# schematic_easyeda.net
KiCad netlist of a schematic drawn in EasyEDA
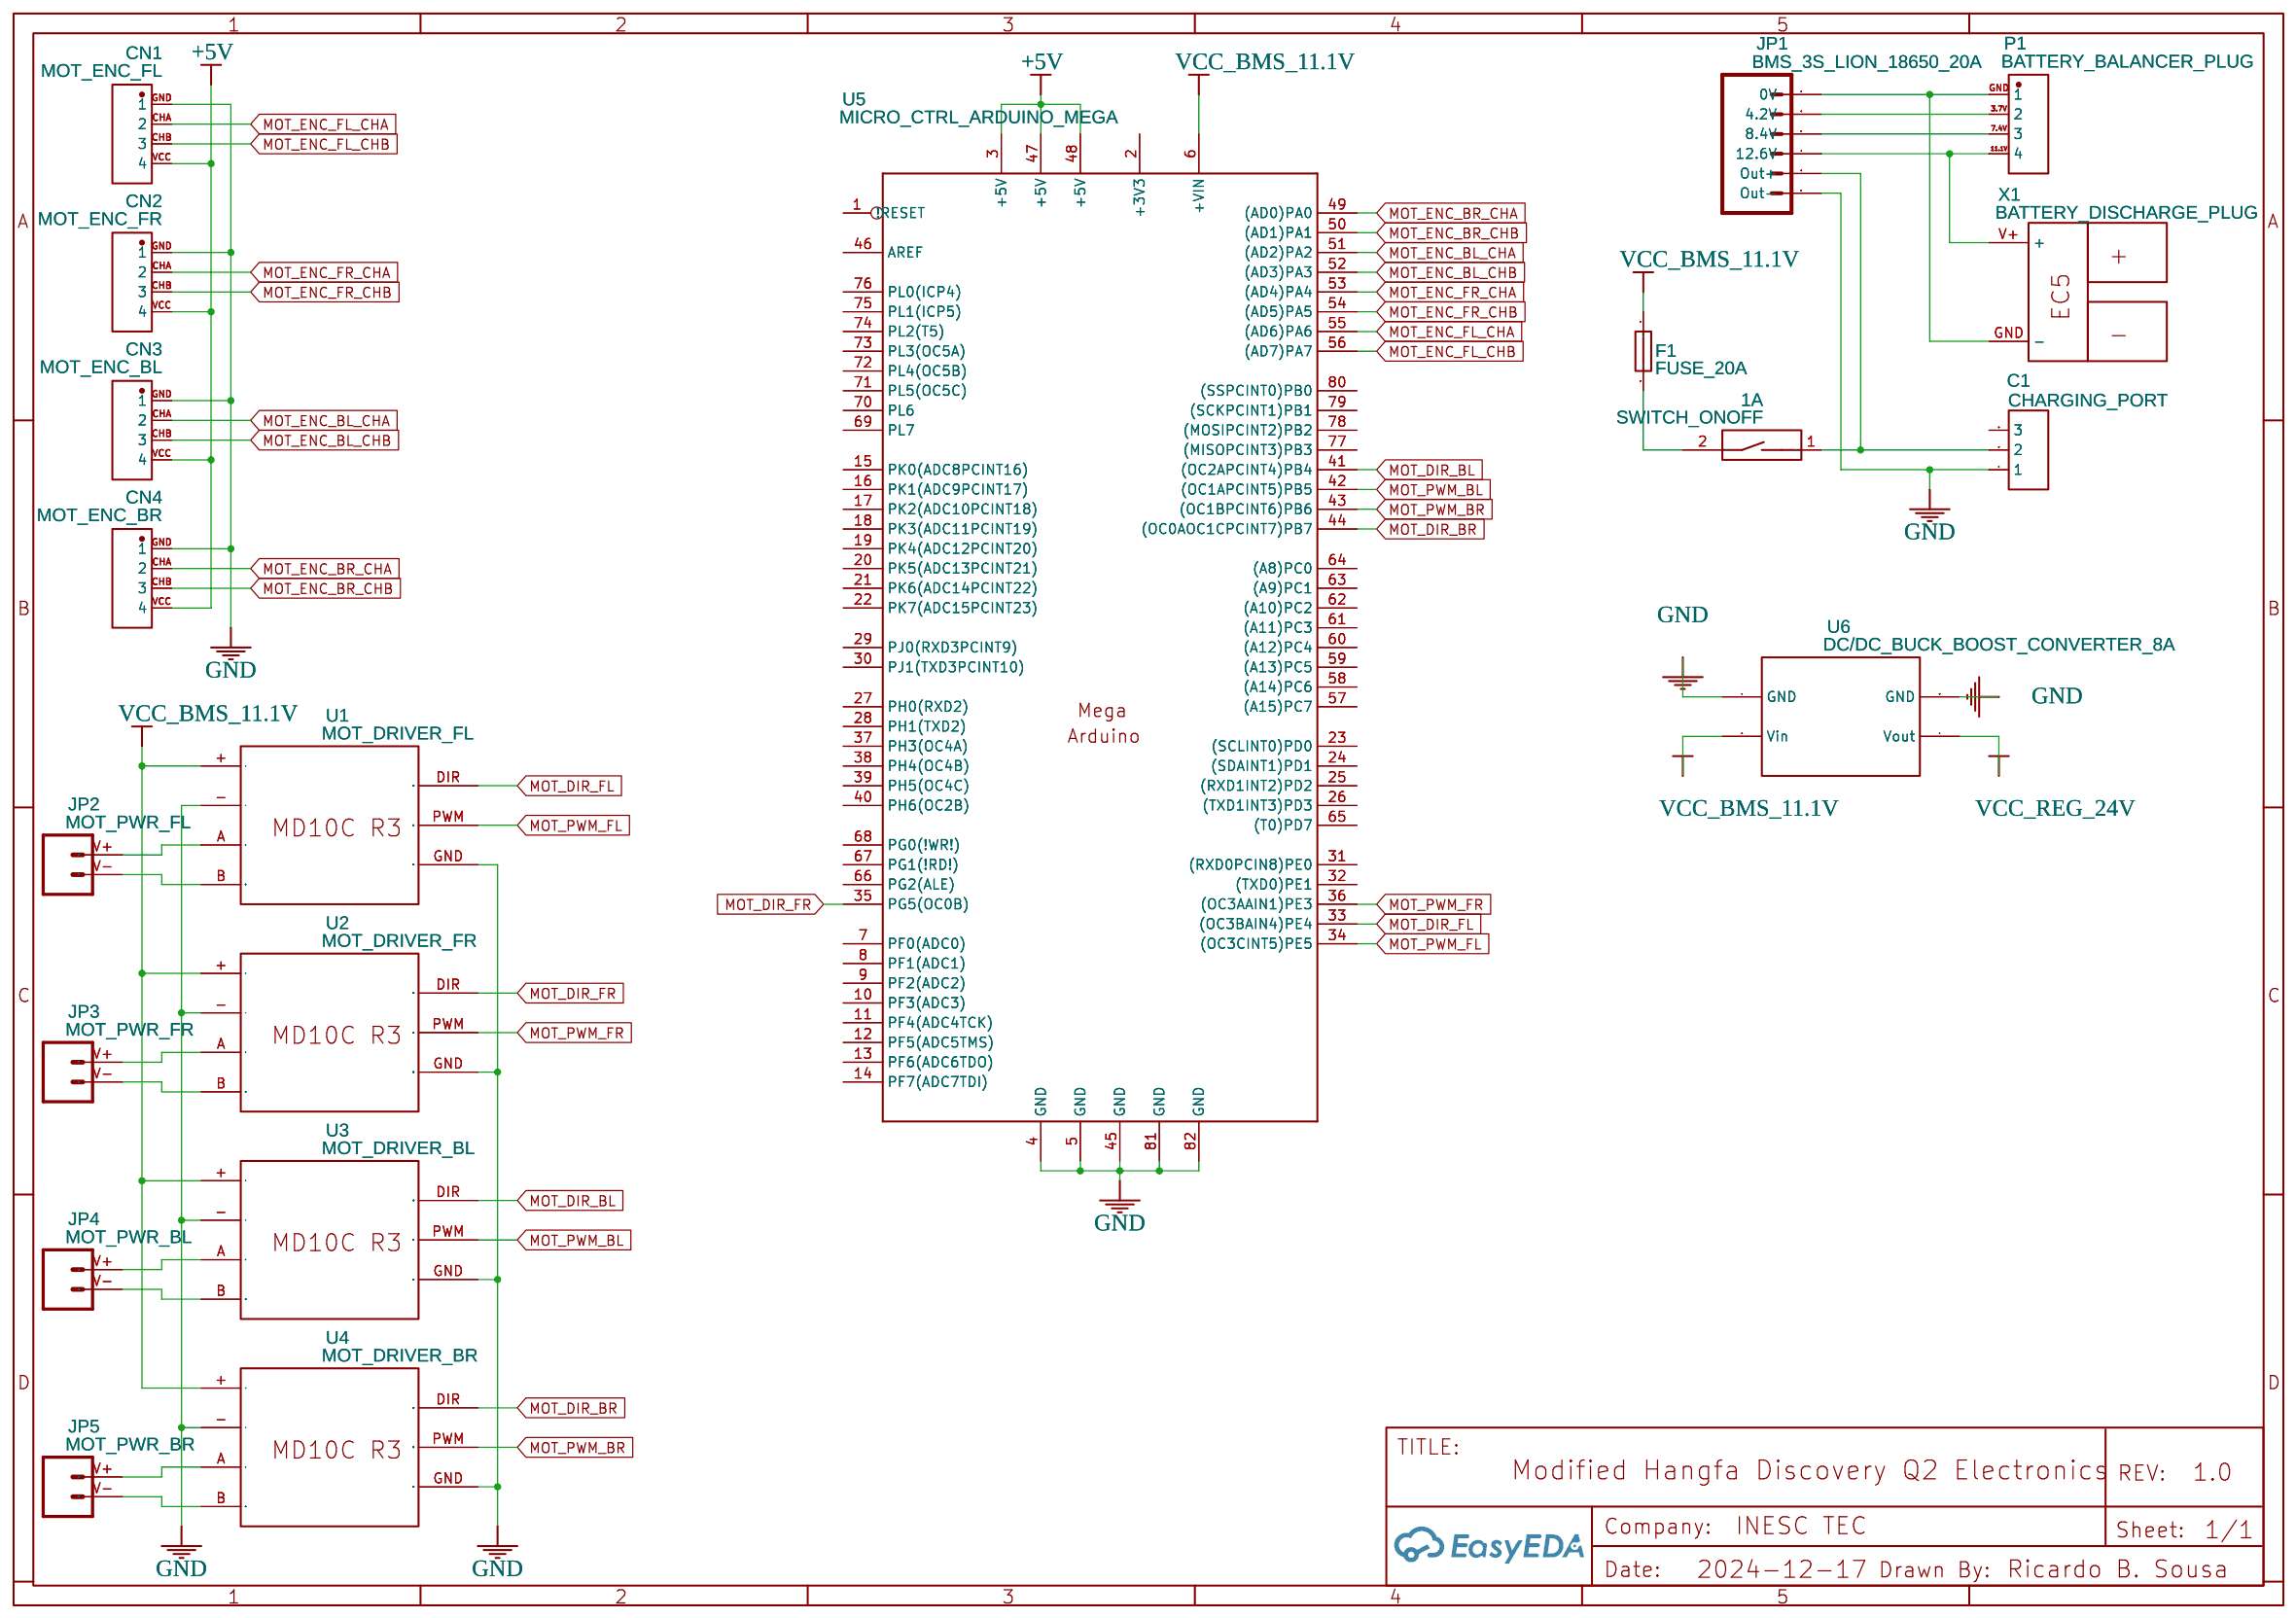
[diagram p0: schematic sheet]

(export (version "E")
  (design (tool "Eeschema 10.0.6"))
  (components
    (comp (ref "1A")
      (value "SWITCH_ONOFF")
      (fields (field (name "Manufacturer Part") "DIP switchEI-08") (field (name "Manufacturer") "DIP"))
      (libsource (lib "") (part "Switch"))
    )
    (comp (ref "C1") (value "CHARGING_PORT") (libsource (lib "") (part "HDR-F-2.54_1x3")))
    (comp (ref "CN1") (value "MOT_ENC_FL") (libsource (lib "") (part "JST-XH2.54 4P")))
    (comp (ref "CN2") (value "MOT_ENC_FR") (libsource (lib "") (part "JST-XH2.54 4P")))
    (comp (ref "CN3") (value "MOT_ENC_BL") (libsource (lib "") (part "JST-XH2.54 4P")))
    (comp (ref "CN4") (value "MOT_ENC_BR") (libsource (lib "") (part "JST-XH2.54 4P")))
    (comp (ref "F1")
      (value "FUSE_20A")
      (fields
        (field (name "Manufacturer Part") "0326025.MXP")
        (field (name "Manufacturer") "Littelfuse(美国力特)")
      )
      (libsource (lib "") (part "Fuse"))
    )
    (comp (ref "JP1") (value "BMS_3S_LION_18650_20A") (libsource (lib "") (part "MY BMS-3S-20A")))
    (comp (ref "JP2") (value "MOT_PWR_FL") (libsource (lib "") (part "M02POLAR")))
    (comp (ref "JP3") (value "MOT_PWR_FR") (libsource (lib "") (part "M02POLAR")))
    (comp (ref "JP4") (value "MOT_PWR_BL") (libsource (lib "") (part "M02POLAR")))
    (comp (ref "JP5") (value "MOT_PWR_BR") (libsource (lib "") (part "M02POLAR")))
    (comp (ref "P1")
      (value "BATTERY_BALANCER_PLUG")
      (fields (field (name "Manufacturer Part") "XH-2.54-4P"))
      (libsource (lib "") (part "XH-2.54-4P"))
    )
    (comp (ref "U1")
      (value "MOT_DRIVER_FL")
      (fields (field (name "Manufacturer") "Cytron"))
      (libsource (lib "") (part "MD10C-R3"))
    )
    (comp (ref "U2")
      (value "MOT_DRIVER_FR")
      (fields (field (name "Manufacturer") "Cytron"))
      (libsource (lib "") (part "MD10C-R3"))
    )
    (comp (ref "U3")
      (value "MOT_DRIVER_BL")
      (fields (field (name "Manufacturer") "Cytron"))
      (libsource (lib "") (part "MD10C-R3"))
    )
    (comp (ref "U4")
      (value "MOT_DRIVER_BR")
      (fields (field (name "Manufacturer") "Cytron"))
      (libsource (lib "") (part "MD10C-R3"))
    )
    (comp (ref "U5") (value "MICRO_CTRL_ARDUINO_MEGA") (libsource (lib "") (part "MEGAARDUINO_1")))
    (comp (ref "U6")
      (value "DC/DC_BUCK_BOOST_CONVERTER_8A")
      (fields (field (name "Manufacturer Part") "DC-DC Converter"))
      (libsource (lib "") (part "DC-DC Converter"))
    )
    (comp (ref "X1") (value "BATTERY_DISCHARGE_PLUG") (libsource (lib "") (part "EC5")))
  )
  (nets
    (net (code "1") (name "+5V") (class "Default")
      (node (ref "CN1") (pin "VCC") (pinfunction "4_VCC") (pintype "unspecified"))
      (node (ref "CN2") (pin "VCC") (pinfunction "4_VCC") (pintype "unspecified"))
      (node (ref "CN3") (pin "VCC") (pinfunction "4_VCC") (pintype "unspecified"))
      (node (ref "CN4") (pin "VCC") (pinfunction "4_VCC") (pintype "unspecified"))
      (node (ref "U5") (pin "3") (pinfunction "+5V_3") (pintype "passive"))
      (node (ref "U5") (pin "47") (pinfunction "+5V_47") (pintype "passive"))
      (node (ref "U5") (pin "48") (pinfunction "+5V_48") (pintype "passive"))
    )
    (net (code "2") (name "GND") (class "Default")
      (node (ref "C1") (pin "1") (pinfunction "1_1") (pintype "unspecified"))
      (node (ref "CN1") (pin "GND") (pinfunction "1_GND") (pintype "unspecified"))
      (node (ref "CN2") (pin "GND") (pinfunction "1_GND") (pintype "unspecified"))
      (node (ref "CN3") (pin "GND") (pinfunction "1_GND") (pintype "unspecified"))
      (node (ref "CN4") (pin "GND") (pinfunction "1_GND") (pintype "unspecified"))
      (node (ref "JP1") (pin "6") (pinfunction "Out-_6") (pintype "unspecified"))
      (node (ref "U1") (pin "-") (pinfunction "-_-") (pintype "unspecified"))
      (node (ref "U1") (pin "GND") (pinfunction "GND_GND") (pintype "unspecified"))
      (node (ref "U2") (pin "-") (pinfunction "-_-") (pintype "unspecified"))
      (node (ref "U2") (pin "GND") (pinfunction "GND_GND") (pintype "unspecified"))
      (node (ref "U3") (pin "-") (pinfunction "-_-") (pintype "unspecified"))
      (node (ref "U3") (pin "GND") (pinfunction "GND_GND") (pintype "unspecified"))
      (node (ref "U4") (pin "-") (pinfunction "-_-") (pintype "unspecified"))
      (node (ref "U4") (pin "GND") (pinfunction "GND_GND") (pintype "unspecified"))
      (node (ref "U5") (pin "4") (pinfunction "GND_4") (pintype "passive"))
      (node (ref "U5") (pin "45") (pinfunction "GND_45") (pintype "passive"))
      (node (ref "U5") (pin "5") (pinfunction "GND_5") (pintype "passive"))
      (node (ref "U5") (pin "81") (pinfunction "GND_81") (pintype "passive"))
      (node (ref "U5") (pin "82") (pinfunction "GND_82") (pintype "passive"))
      (node (ref "U6") (pin "1") (pinfunction "GND_1") (pintype "unspecified"))
      (node (ref "U6") (pin "3") (pinfunction "GND_3") (pintype "unspecified"))
    )
    (net (code "3") (name "MOT_DIR_BL") (class "Default")
      (node (ref "U3") (pin "DIR") (pinfunction "DIR_DIR") (pintype "unspecified"))
      (node (ref "U5") (pin "41") (pinfunction "(OC2APCINT4)PB4_41") (pintype "unspecified"))
    )
    (net (code "4") (name "MOT_DIR_BR") (class "Default")
      (node (ref "U4") (pin "DIR") (pinfunction "DIR_DIR") (pintype "unspecified"))
      (node (ref "U5") (pin "44") (pinfunction "(OC0AOC1CPCINT7)PB7_44") (pintype "unspecified"))
    )
    (net (code "5") (name "MOT_DIR_FL") (class "Default")
      (node (ref "U1") (pin "DIR") (pinfunction "DIR_DIR") (pintype "unspecified"))
      (node (ref "U5") (pin "33") (pinfunction "(OC3BAIN4)PE4_33") (pintype "unspecified"))
    )
    (net (code "6") (name "MOT_DIR_FR") (class "Default")
      (node (ref "U2") (pin "DIR") (pinfunction "DIR_DIR") (pintype "unspecified"))
      (node (ref "U5") (pin "35") (pinfunction "PG5(OC0B)_35") (pintype "unspecified"))
    )
    (net (code "7") (name "MOT_ENC_BL_CHA") (class "Default")
      (node (ref "CN3") (pin "CHA") (pinfunction "2_CHA") (pintype "unspecified"))
      (node (ref "U5") (pin "51") (pinfunction "(AD2)PA2_51") (pintype "unspecified"))
    )
    (net (code "8") (name "MOT_ENC_BL_CHB") (class "Default")
      (node (ref "CN3") (pin "CHB") (pinfunction "3_CHB") (pintype "unspecified"))
      (node (ref "U5") (pin "52") (pinfunction "(AD3)PA3_52") (pintype "unspecified"))
    )
    (net (code "9") (name "MOT_ENC_BR_CHA") (class "Default")
      (node (ref "CN4") (pin "CHA") (pinfunction "2_CHA") (pintype "unspecified"))
      (node (ref "U5") (pin "49") (pinfunction "(AD0)PA0_49") (pintype "unspecified"))
    )
    (net (code "10") (name "MOT_ENC_BR_CHB") (class "Default")
      (node (ref "CN4") (pin "CHB") (pinfunction "3_CHB") (pintype "unspecified"))
      (node (ref "U5") (pin "50") (pinfunction "(AD1)PA1_50") (pintype "unspecified"))
    )
    (net (code "11") (name "MOT_ENC_FL_CHA") (class "Default")
      (node (ref "CN1") (pin "CHA") (pinfunction "2_CHA") (pintype "unspecified"))
      (node (ref "U5") (pin "55") (pinfunction "(AD6)PA6_55") (pintype "unspecified"))
    )
    (net (code "12") (name "MOT_ENC_FL_CHB") (class "Default")
      (node (ref "CN1") (pin "CHB") (pinfunction "3_CHB") (pintype "unspecified"))
      (node (ref "U5") (pin "56") (pinfunction "(AD7)PA7_56") (pintype "unspecified"))
    )
    (net (code "13") (name "MOT_ENC_FR_CHA") (class "Default")
      (node (ref "CN2") (pin "CHA") (pinfunction "2_CHA") (pintype "unspecified"))
      (node (ref "U5") (pin "53") (pinfunction "(AD4)PA4_53") (pintype "unspecified"))
    )
    (net (code "14") (name "MOT_ENC_FR_CHB") (class "Default")
      (node (ref "CN2") (pin "CHB") (pinfunction "3_CHB") (pintype "unspecified"))
      (node (ref "U5") (pin "54") (pinfunction "(AD5)PA5_54") (pintype "unspecified"))
    )
    (net (code "15") (name "MOT_PWM_BL") (class "Default")
      (node (ref "U3") (pin "PWM") (pinfunction "PWM_PWM") (pintype "unspecified"))
      (node (ref "U5") (pin "42") (pinfunction "(OC1APCINT5)PB5_42") (pintype "unspecified"))
    )
    (net (code "16") (name "MOT_PWM_BR") (class "Default")
      (node (ref "U4") (pin "PWM") (pinfunction "PWM_PWM") (pintype "unspecified"))
      (node (ref "U5") (pin "43") (pinfunction "(OC1BPCINT6)PB6_43") (pintype "unspecified"))
    )
    (net (code "17") (name "MOT_PWM_FL") (class "Default")
      (node (ref "U1") (pin "PWM") (pinfunction "PWM_PWM") (pintype "unspecified"))
      (node (ref "U5") (pin "34") (pinfunction "(OC3CINT5)PE5_34") (pintype "unspecified"))
    )
    (net (code "18") (name "MOT_PWM_FR") (class "Default")
      (node (ref "U2") (pin "PWM") (pinfunction "PWM_PWM") (pintype "unspecified"))
      (node (ref "U5") (pin "36") (pinfunction "(OC3AAIN1)PE3_36") (pintype "unspecified"))
    )
    (net (code "19") (name "Net-(1A-Pad2)") (class "Default")
      (node (ref "1A") (pin "2") (pinfunction "2_2") (pintype "unspecified"))
      (node (ref "F1") (pin "2") (pinfunction "2_2") (pintype "unspecified"))
    )
    (net (code "20") (name "Net-(JP1-0V)") (class "Default")
      (node (ref "JP1") (pin "1") (pinfunction "0V_1") (pintype "unspecified"))
      (node (ref "P1") (pin "GND") (pinfunction "1_GND") (pintype "unspecified"))
      (node (ref "X1") (pin "GND") (pinfunction "-_GND") (pintype "unspecified"))
    )
    (net (code "21") (name "Net-(JP1-4.2V)") (class "Default")
      (node (ref "JP1") (pin "2") (pinfunction "4.2V_2") (pintype "unspecified"))
      (node (ref "P1") (pin "3.7V") (pinfunction "2_3.7V") (pintype "unspecified"))
    )
    (net (code "22") (name "Net-(JP1-8.4V)") (class "Default")
      (node (ref "JP1") (pin "3") (pinfunction "8.4V_3") (pintype "unspecified"))
      (node (ref "P1") (pin "7.4V") (pinfunction "3_7.4V") (pintype "unspecified"))
    )
    (net (code "23") (name "Net-(JP1-12.6V)") (class "Default")
      (node (ref "JP1") (pin "4") (pinfunction "12.6V_4") (pintype "unspecified"))
      (node (ref "P1") (pin "11.1V") (pinfunction "4_11.1V") (pintype "unspecified"))
      (node (ref "X1") (pin "V+") (pinfunction "+_V+") (pintype "unspecified"))
    )
    (net (code "24") (name "Net-(JP1-Out+)") (class "Default")
      (node (ref "1A") (pin "1") (pinfunction "1_1") (pintype "unspecified"))
      (node (ref "C1") (pin "2") (pinfunction "2_2") (pintype "unspecified"))
      (node (ref "JP1") (pin "5") (pinfunction "Out+_5") (pintype "unspecified"))
    )
    (net (code "25") (name "Net-(JP2-1)") (class "Default")
      (node (ref "JP2") (pin "V-") (pinfunction "1_V-") (pintype "bidirectional"))
      (node (ref "U1") (pin "B") (pinfunction "B_B") (pintype "unspecified"))
    )
    (net (code "26") (name "Net-(JP2-2)") (class "Default")
      (node (ref "JP2") (pin "V+") (pinfunction "2_V+") (pintype "bidirectional"))
      (node (ref "U1") (pin "A") (pinfunction "A_A") (pintype "unspecified"))
    )
    (net (code "27") (name "Net-(JP3-1)") (class "Default")
      (node (ref "JP3") (pin "V-") (pinfunction "1_V-") (pintype "bidirectional"))
      (node (ref "U2") (pin "B") (pinfunction "B_B") (pintype "unspecified"))
    )
    (net (code "28") (name "Net-(JP3-2)") (class "Default")
      (node (ref "JP3") (pin "V+") (pinfunction "2_V+") (pintype "bidirectional"))
      (node (ref "U2") (pin "A") (pinfunction "A_A") (pintype "unspecified"))
    )
    (net (code "29") (name "Net-(JP4-1)") (class "Default")
      (node (ref "JP4") (pin "V-") (pinfunction "1_V-") (pintype "bidirectional"))
      (node (ref "U3") (pin "B") (pinfunction "B_B") (pintype "unspecified"))
    )
    (net (code "30") (name "Net-(JP4-2)") (class "Default")
      (node (ref "JP4") (pin "V+") (pinfunction "2_V+") (pintype "bidirectional"))
      (node (ref "U3") (pin "A") (pinfunction "A_A") (pintype "unspecified"))
    )
    (net (code "31") (name "Net-(JP5-1)") (class "Default")
      (node (ref "JP5") (pin "V-") (pinfunction "1_V-") (pintype "bidirectional"))
      (node (ref "U4") (pin "B") (pinfunction "B_B") (pintype "unspecified"))
    )
    (net (code "32") (name "Net-(JP5-2)") (class "Default")
      (node (ref "JP5") (pin "V+") (pinfunction "2_V+") (pintype "bidirectional"))
      (node (ref "U4") (pin "A") (pinfunction "A_A") (pintype "unspecified"))
    )
    (net (code "33") (name "VCC_BMS_11.1V") (class "Default")
      (node (ref "F1") (pin "1") (pinfunction "1_1") (pintype "unspecified"))
      (node (ref "U1") (pin "+") (pinfunction "+_+") (pintype "unspecified"))
      (node (ref "U2") (pin "+") (pinfunction "+_+") (pintype "unspecified"))
      (node (ref "U3") (pin "+") (pinfunction "+_+") (pintype "unspecified"))
      (node (ref "U4") (pin "+") (pinfunction "+_+") (pintype "unspecified"))
      (node (ref "U5") (pin "6") (pinfunction "+VIN_6") (pintype "passive"))
      (node (ref "U6") (pin "2") (pinfunction "Vin_2") (pintype "unspecified"))
    )
    (net (code "34") (name "VCC_REG_24V") (class "Default")
      (node (ref "U6") (pin "4") (pinfunction "Vout_4") (pintype "unspecified"))
    )
    (net (code "35") (name "unconnected-(C1-Pad3)") (class "Default")
      (node (ref "C1") (pin "3") (pinfunction "3_3") (pintype "unspecified"))
    )
    (net (code "36") (name "unconnected-(U5-!RESET-Pad1)") (class "Default")
      (node (ref "U5") (pin "1") (pinfunction "!RESET_1") (pintype "unspecified"))
    )
    (net (code "37") (name "unconnected-(U5-(A8)PC0-Pad64)") (class "Default")
      (node (ref "U5") (pin "64") (pinfunction "(A8)PC0_64") (pintype "unspecified"))
    )
    (net (code "38") (name "unconnected-(U5-(A9)PC1-Pad63)") (class "Default")
      (node (ref "U5") (pin "63") (pinfunction "(A9)PC1_63") (pintype "unspecified"))
    )
    (net (code "39") (name "unconnected-(U5-(A10)PC2-Pad62)") (class "Default")
      (node (ref "U5") (pin "62") (pinfunction "(A10)PC2_62") (pintype "unspecified"))
    )
    (net (code "40") (name "unconnected-(U5-(A11)PC3-Pad61)") (class "Default")
      (node (ref "U5") (pin "61") (pinfunction "(A11)PC3_61") (pintype "unspecified"))
    )
    (net (code "41") (name "unconnected-(U5-(A12)PC4-Pad60)") (class "Default")
      (node (ref "U5") (pin "60") (pinfunction "(A12)PC4_60") (pintype "unspecified"))
    )
    (net (code "42") (name "unconnected-(U5-(A13)PC5-Pad59)") (class "Default")
      (node (ref "U5") (pin "59") (pinfunction "(A13)PC5_59") (pintype "unspecified"))
    )
    (net (code "43") (name "unconnected-(U5-(A14)PC6-Pad58)") (class "Default")
      (node (ref "U5") (pin "58") (pinfunction "(A14)PC6_58") (pintype "unspecified"))
    )
    (net (code "44") (name "unconnected-(U5-(A15)PC7-Pad57)") (class "Default")
      (node (ref "U5") (pin "57") (pinfunction "(A15)PC7_57") (pintype "unspecified"))
    )
    (net (code "45") (name "unconnected-(U5-(MISOPCINT3)PB3-Pad77)") (class "Default")
      (node (ref "U5") (pin "77") (pinfunction "(MISOPCINT3)PB3_77") (pintype "unspecified"))
    )
    (net (code "46") (name "unconnected-(U5-(MOSIPCINT2)PB2-Pad78)") (class "Default")
      (node (ref "U5") (pin "78") (pinfunction "(MOSIPCINT2)PB2_78") (pintype "unspecified"))
    )
    (net (code "47") (name "unconnected-(U5-(RXD0PCIN8)PE0-Pad31)") (class "Default")
      (node (ref "U5") (pin "31") (pinfunction "(RXD0PCIN8)PE0_31") (pintype "unspecified"))
    )
    (net (code "48") (name "unconnected-(U5-(RXD1INT2)PD2-Pad25)") (class "Default")
      (node (ref "U5") (pin "25") (pinfunction "(RXD1INT2)PD2_25") (pintype "unspecified"))
    )
    (net (code "49") (name "unconnected-(U5-(SCKPCINT1)PB1-Pad79)") (class "Default")
      (node (ref "U5") (pin "79") (pinfunction "(SCKPCINT1)PB1_79") (pintype "unspecified"))
    )
    (net (code "50") (name "unconnected-(U5-(SCLINT0)PD0-Pad23)") (class "Default")
      (node (ref "U5") (pin "23") (pinfunction "(SCLINT0)PD0_23") (pintype "unspecified"))
    )
    (net (code "51") (name "unconnected-(U5-(SDAINT1)PD1-Pad24)") (class "Default")
      (node (ref "U5") (pin "24") (pinfunction "(SDAINT1)PD1_24") (pintype "unspecified"))
    )
    (net (code "52") (name "unconnected-(U5-(SSPCINT0)PB0-Pad80)") (class "Default")
      (node (ref "U5") (pin "80") (pinfunction "(SSPCINT0)PB0_80") (pintype "unspecified"))
    )
    (net (code "53") (name "unconnected-(U5-(T0)PD7-Pad65)") (class "Default")
      (node (ref "U5") (pin "65") (pinfunction "(T0)PD7_65") (pintype "unspecified"))
    )
    (net (code "54") (name "unconnected-(U5-(TXD0)PE1-Pad32)") (class "Default")
      (node (ref "U5") (pin "32") (pinfunction "(TXD0)PE1_32") (pintype "unspecified"))
    )
    (net (code "55") (name "unconnected-(U5-(TXD1INT3)PD3-Pad26)") (class "Default")
      (node (ref "U5") (pin "26") (pinfunction "(TXD1INT3)PD3_26") (pintype "unspecified"))
    )
    (net (code "56") (name "unconnected-(U5-+3V3-Pad2)") (class "Default")
      (node (ref "U5") (pin "2") (pinfunction "+3V3_2") (pintype "passive"))
    )
    (net (code "57") (name "unconnected-(U5-AREF-Pad46)") (class "Default")
      (node (ref "U5") (pin "46") (pinfunction "AREF_46") (pintype "unspecified"))
    )
    (net (code "58") (name "unconnected-(U5-PF0(ADC0)-Pad7)") (class "Default")
      (node (ref "U5") (pin "7") (pinfunction "PF0(ADC0)_7") (pintype "unspecified"))
    )
    (net (code "59") (name "unconnected-(U5-PF1(ADC1)-Pad8)") (class "Default")
      (node (ref "U5") (pin "8") (pinfunction "PF1(ADC1)_8") (pintype "unspecified"))
    )
    (net (code "60") (name "unconnected-(U5-PF2(ADC2)-Pad9)") (class "Default")
      (node (ref "U5") (pin "9") (pinfunction "PF2(ADC2)_9") (pintype "unspecified"))
    )
    (net (code "61") (name "unconnected-(U5-PF3(ADC3)-Pad10)") (class "Default")
      (node (ref "U5") (pin "10") (pinfunction "PF3(ADC3)_10") (pintype "unspecified"))
    )
    (net (code "62") (name "unconnected-(U5-PF4(ADC4TCK)-Pad11)") (class "Default")
      (node (ref "U5") (pin "11") (pinfunction "PF4(ADC4TCK)_11") (pintype "unspecified"))
    )
    (net (code "63") (name "unconnected-(U5-PF5(ADC5TMS)-Pad12)") (class "Default")
      (node (ref "U5") (pin "12") (pinfunction "PF5(ADC5TMS)_12") (pintype "unspecified"))
    )
    (net (code "64") (name "unconnected-(U5-PF6(ADC6TDO)-Pad13)") (class "Default")
      (node (ref "U5") (pin "13") (pinfunction "PF6(ADC6TDO)_13") (pintype "unspecified"))
    )
    (net (code "65") (name "unconnected-(U5-PF7(ADC7TDI)-Pad14)") (class "Default")
      (node (ref "U5") (pin "14") (pinfunction "PF7(ADC7TDI)_14") (pintype "unspecified"))
    )
    (net (code "66") (name "unconnected-(U5-PG0(!WR!)-Pad68)") (class "Default")
      (node (ref "U5") (pin "68") (pinfunction "PG0(!WR!)_68") (pintype "unspecified"))
    )
    (net (code "67") (name "unconnected-(U5-PG1(!RD!)-Pad67)") (class "Default")
      (node (ref "U5") (pin "67") (pinfunction "PG1(!RD!)_67") (pintype "unspecified"))
    )
    (net (code "68") (name "unconnected-(U5-PG2(ALE)-Pad66)") (class "Default")
      (node (ref "U5") (pin "66") (pinfunction "PG2(ALE)_66") (pintype "unspecified"))
    )
    (net (code "69") (name "unconnected-(U5-PH0(RXD2)-Pad27)") (class "Default")
      (node (ref "U5") (pin "27") (pinfunction "PH0(RXD2)_27") (pintype "unspecified"))
    )
    (net (code "70") (name "unconnected-(U5-PH1(TXD2)-Pad28)") (class "Default")
      (node (ref "U5") (pin "28") (pinfunction "PH1(TXD2)_28") (pintype "unspecified"))
    )
    (net (code "71") (name "unconnected-(U5-PH3(OC4A)-Pad37)") (class "Default")
      (node (ref "U5") (pin "37") (pinfunction "PH3(OC4A)_37") (pintype "unspecified"))
    )
    (net (code "72") (name "unconnected-(U5-PH4(OC4B)-Pad38)") (class "Default")
      (node (ref "U5") (pin "38") (pinfunction "PH4(OC4B)_38") (pintype "unspecified"))
    )
    (net (code "73") (name "unconnected-(U5-PH5(OC4C)-Pad39)") (class "Default")
      (node (ref "U5") (pin "39") (pinfunction "PH5(OC4C)_39") (pintype "unspecified"))
    )
    (net (code "74") (name "unconnected-(U5-PH6(OC2B)-Pad40)") (class "Default")
      (node (ref "U5") (pin "40") (pinfunction "PH6(OC2B)_40") (pintype "unspecified"))
    )
    (net (code "75") (name "unconnected-(U5-PJ0(RXD3PCINT9)-Pad29)") (class "Default")
      (node (ref "U5") (pin "29") (pinfunction "PJ0(RXD3PCINT9)_29") (pintype "unspecified"))
    )
    (net (code "76") (name "unconnected-(U5-PJ1(TXD3PCINT10)-Pad30)") (class "Default")
      (node (ref "U5") (pin "30") (pinfunction "PJ1(TXD3PCINT10)_30") (pintype "unspecified"))
    )
    (net (code "77") (name "unconnected-(U5-PK0(ADC8PCINT16)-Pad15)") (class "Default")
      (node (ref "U5") (pin "15") (pinfunction "PK0(ADC8PCINT16)_15") (pintype "unspecified"))
    )
    (net (code "78") (name "unconnected-(U5-PK1(ADC9PCINT17)-Pad16)") (class "Default")
      (node (ref "U5") (pin "16") (pinfunction "PK1(ADC9PCINT17)_16") (pintype "unspecified"))
    )
    (net (code "79") (name "unconnected-(U5-PK2(ADC10PCINT18)-Pad17)") (class "Default")
      (node (ref "U5") (pin "17") (pinfunction "PK2(ADC10PCINT18)_17") (pintype "unspecified"))
    )
    (net (code "80") (name "unconnected-(U5-PK3(ADC11PCINT19)-Pad18)") (class "Default")
      (node (ref "U5") (pin "18") (pinfunction "PK3(ADC11PCINT19)_18") (pintype "unspecified"))
    )
    (net (code "81") (name "unconnected-(U5-PK4(ADC12PCINT20)-Pad19)") (class "Default")
      (node (ref "U5") (pin "19") (pinfunction "PK4(ADC12PCINT20)_19") (pintype "unspecified"))
    )
    (net (code "82") (name "unconnected-(U5-PK5(ADC13PCINT21)-Pad20)") (class "Default")
      (node (ref "U5") (pin "20") (pinfunction "PK5(ADC13PCINT21)_20") (pintype "unspecified"))
    )
    (net (code "83") (name "unconnected-(U5-PK6(ADC14PCINT22)-Pad21)") (class "Default")
      (node (ref "U5") (pin "21") (pinfunction "PK6(ADC14PCINT22)_21") (pintype "unspecified"))
    )
    (net (code "84") (name "unconnected-(U5-PK7(ADC15PCINT23)-Pad22)") (class "Default")
      (node (ref "U5") (pin "22") (pinfunction "PK7(ADC15PCINT23)_22") (pintype "unspecified"))
    )
    (net (code "85") (name "unconnected-(U5-PL0(ICP4)-Pad76)") (class "Default")
      (node (ref "U5") (pin "76") (pinfunction "PL0(ICP4)_76") (pintype "unspecified"))
    )
    (net (code "86") (name "unconnected-(U5-PL1(ICP5)-Pad75)") (class "Default")
      (node (ref "U5") (pin "75") (pinfunction "PL1(ICP5)_75") (pintype "unspecified"))
    )
    (net (code "87") (name "unconnected-(U5-PL2(T5)-Pad74)") (class "Default")
      (node (ref "U5") (pin "74") (pinfunction "PL2(T5)_74") (pintype "unspecified"))
    )
    (net (code "88") (name "unconnected-(U5-PL3(OC5A)-Pad73)") (class "Default")
      (node (ref "U5") (pin "73") (pinfunction "PL3(OC5A)_73") (pintype "unspecified"))
    )
    (net (code "89") (name "unconnected-(U5-PL4(OC5B)-Pad72)") (class "Default")
      (node (ref "U5") (pin "72") (pinfunction "PL4(OC5B)_72") (pintype "unspecified"))
    )
    (net (code "90") (name "unconnected-(U5-PL5(OC5C)-Pad71)") (class "Default")
      (node (ref "U5") (pin "71") (pinfunction "PL5(OC5C)_71") (pintype "unspecified"))
    )
    (net (code "91") (name "unconnected-(U5-PL6-Pad70)") (class "Default")
      (node (ref "U5") (pin "70") (pinfunction "PL6_70") (pintype "unspecified"))
    )
    (net (code "92") (name "unconnected-(U5-PL7-Pad69)") (class "Default")
      (node (ref "U5") (pin "69") (pinfunction "PL7_69") (pintype "unspecified"))
    )
  )
)
